# bee.net
KiCad netlist of a schematic drawn in Altium Designer
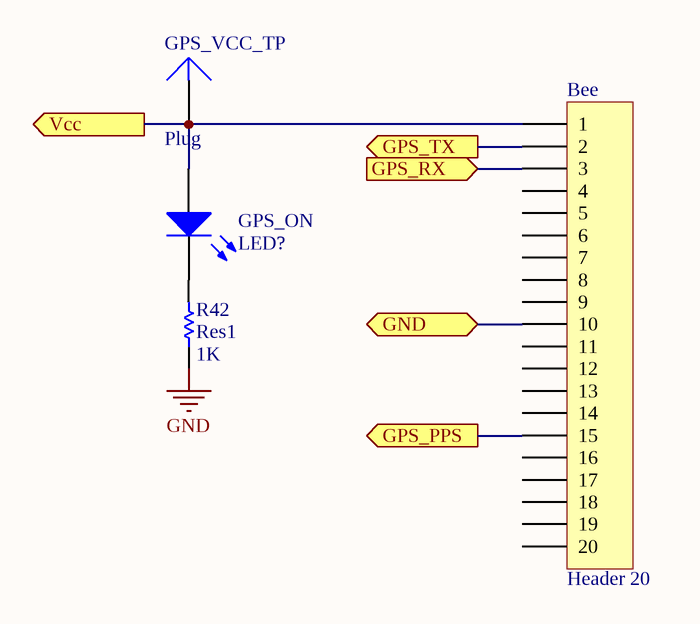
[diagram p0: bee.SchDoc]

(export (version "E")
  (design (tool "Eeschema 10.0.6"))
  (components
    (comp (ref "Bee")
      (value "Header 20")
      (footprint "BeeSlot")
      (description "Header, 20-Pin")
      (fields (field (name "PUBLISHER") "Altium Limited"))
      (libsource (lib "Miscellaneous Connectors") (part "Header 20"))
    )
    (comp (ref "GPS_ON")
      (value "LED?")
      (footprint "C0603")
      (description "Typical INFRARED GaAs LED")
      (fields (field (name "PUBLISHER") "Altium Limited"))
      (libsource (lib "any") (part "LED0"))
    )
    (comp (ref "GPS_VCC_TP")
      (value "Plug")
      (footprint "PIN1")
      (fields (field (name "PUBLISHER") "Altium Limited"))
      (libsource (lib "Miscellaneous Connectors") (part "Plug"))
    )
    (comp (ref "R42")
      (value "Res1")
      (footprint "R0603")
      (description "Resistor")
      (fields (field (name "ALTIUM_VALUE") "1K") (field (name "PUBLISHER") "Altium Limited"))
      (libsource (lib "any") (part "Res1"))
    )
  )
  (nets
    (net (code "1") (name "/GPS_PPS") (class "Default")
      (node (ref "Bee") (pin "15") (pinfunction "15_15") (pintype "passive"))
    )
    (net (code "2") (name "/GPS_RX") (class "Default")
      (node (ref "Bee") (pin "3") (pinfunction "3_3") (pintype "passive"))
    )
    (net (code "3") (name "/GPS_TX") (class "Default")
      (node (ref "Bee") (pin "2") (pinfunction "2_2") (pintype "passive"))
    )
    (net (code "4") (name "/Vcc") (class "Default")
      (node (ref "Bee") (pin "1") (pinfunction "1_1") (pintype "passive"))
      (node (ref "GPS_ON") (pin "1") (pinfunction "A_1") (pintype "passive"))
      (node (ref "GPS_VCC_TP") (pin "1") (pinfunction "1_1") (pintype "passive"))
    )
    (net (code "5") (name "GND") (class "Default")
      (node (ref "Bee") (pin "10") (pinfunction "10_10") (pintype "passive"))
      (node (ref "R42") (pin "1") (pinfunction "1_1") (pintype "passive"))
    )
    (net (code "6") (name "Net-(GPS_ON-K)") (class "Default")
      (node (ref "GPS_ON") (pin "2") (pinfunction "K_2") (pintype "passive"))
      (node (ref "R42") (pin "2") (pinfunction "2_2") (pintype "passive"))
    )
    (net (code "7") (name "unconnected-(Bee-Pad4)") (class "Default")
      (node (ref "Bee") (pin "4") (pinfunction "4_4") (pintype "passive"))
    )
    (net (code "8") (name "unconnected-(Bee-Pad5)") (class "Default")
      (node (ref "Bee") (pin "5") (pinfunction "5_5") (pintype "passive"))
    )
    (net (code "9") (name "unconnected-(Bee-Pad6)") (class "Default")
      (node (ref "Bee") (pin "6") (pinfunction "6_6") (pintype "passive"))
    )
    (net (code "10") (name "unconnected-(Bee-Pad7)") (class "Default")
      (node (ref "Bee") (pin "7") (pinfunction "7_7") (pintype "passive"))
    )
    (net (code "11") (name "unconnected-(Bee-Pad8)") (class "Default")
      (node (ref "Bee") (pin "8") (pinfunction "8_8") (pintype "passive"))
    )
    (net (code "12") (name "unconnected-(Bee-Pad9)") (class "Default")
      (node (ref "Bee") (pin "9") (pinfunction "9_9") (pintype "passive"))
    )
    (net (code "13") (name "unconnected-(Bee-Pad11)") (class "Default")
      (node (ref "Bee") (pin "11") (pinfunction "11_11") (pintype "passive"))
    )
    (net (code "14") (name "unconnected-(Bee-Pad12)") (class "Default")
      (node (ref "Bee") (pin "12") (pinfunction "12_12") (pintype "passive"))
    )
    (net (code "15") (name "unconnected-(Bee-Pad13)") (class "Default")
      (node (ref "Bee") (pin "13") (pinfunction "13_13") (pintype "passive"))
    )
    (net (code "16") (name "unconnected-(Bee-Pad14)") (class "Default")
      (node (ref "Bee") (pin "14") (pinfunction "14_14") (pintype "passive"))
    )
    (net (code "17") (name "unconnected-(Bee-Pad16)") (class "Default")
      (node (ref "Bee") (pin "16") (pinfunction "16_16") (pintype "passive"))
    )
    (net (code "18") (name "unconnected-(Bee-Pad17)") (class "Default")
      (node (ref "Bee") (pin "17") (pinfunction "17_17") (pintype "passive"))
    )
    (net (code "19") (name "unconnected-(Bee-Pad18)") (class "Default")
      (node (ref "Bee") (pin "18") (pinfunction "18_18") (pintype "passive"))
    )
    (net (code "20") (name "unconnected-(Bee-Pad19)") (class "Default")
      (node (ref "Bee") (pin "19") (pinfunction "19_19") (pintype "passive"))
    )
    (net (code "21") (name "unconnected-(Bee-Pad20)") (class "Default")
      (node (ref "Bee") (pin "20") (pinfunction "20_20") (pintype "passive"))
    )
  )
)
